# FLS_Hamamatsu_A.net
KiCad netlist of a schematic drawn in Altium Designer
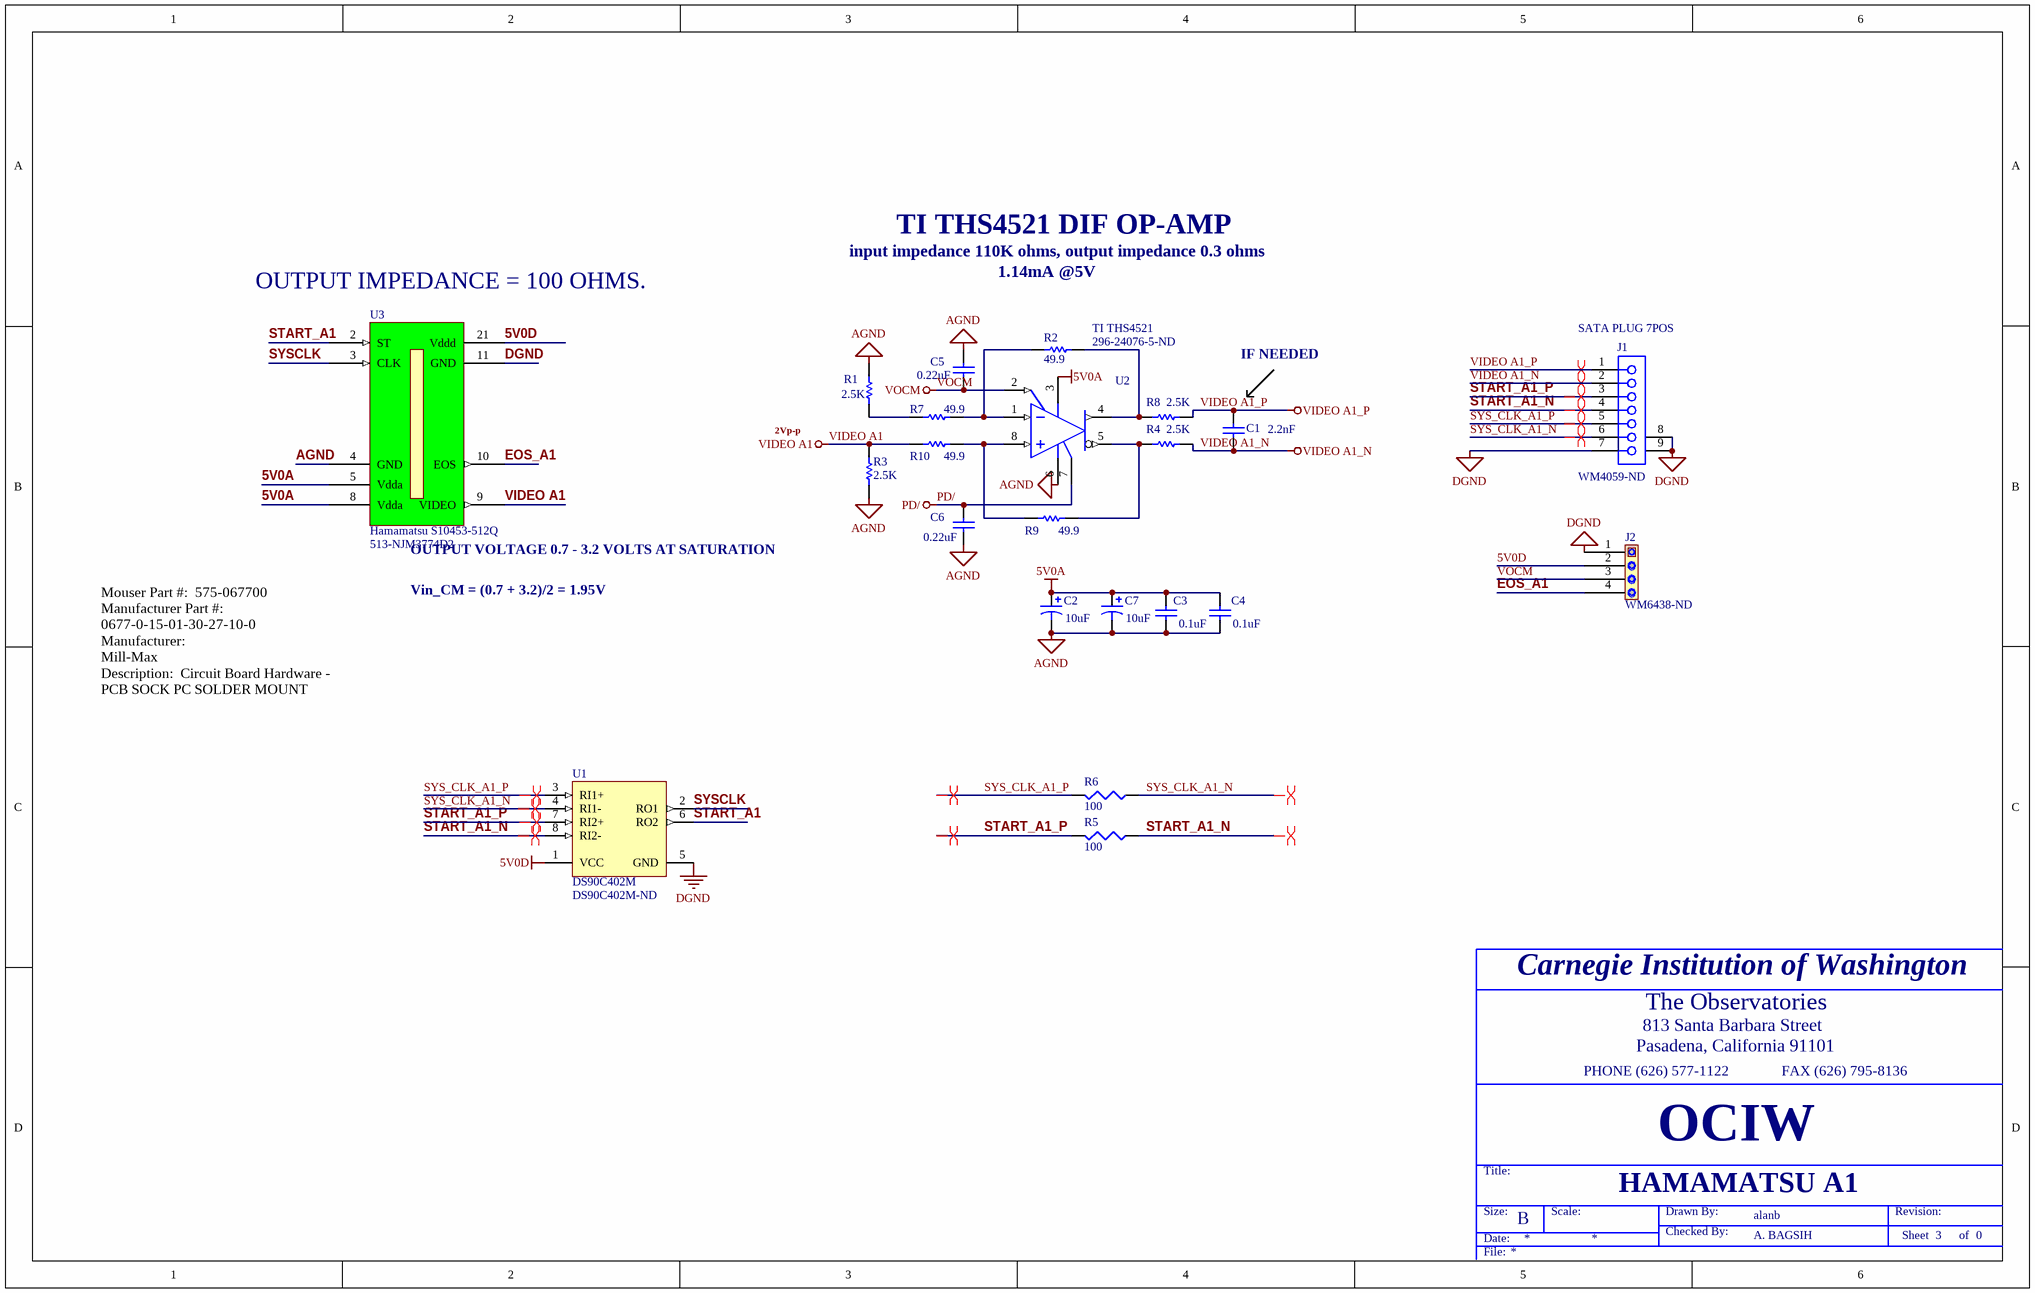
[diagram p0: FLS Hamamatsu_A.SchDoc]

(export (version "E")
  (design (tool "Eeschema 10.0.6"))
  (components
    (comp (ref "C1")
      (value "2.2nF")
      (footprint "0805 SLIM")
      (description "Capacitor")
      (fields (field (name "Comment") "Cap") (field (name "PUBLISHER") "Altium Limited"))
      (libsource (lib "Miscellaneous Devices") (part "Cap"))
    )
    (comp (ref "C2")
      (value "10uF")
      (footprint "1206")
      (description "CAP TANT 10UF 16V 20% 1206")
      (fields (field (name "Comment") "Cap Pol3") (field (name "PUBLISHER") "Altium Limited"))
      (libsource (lib "Miscellaneous Devices") (part "Cap Pol3"))
    )
    (comp (ref "C3")
      (value "0.1uF")
      (footprint "0805 SLIM")
      (description "Capacitor")
      (fields (field (name "Comment") "Cap") (field (name "PUBLISHER") "Altium Limited"))
      (libsource (lib "Miscellaneous Devices") (part "Cap"))
    )
    (comp (ref "C4")
      (value "0.1uF")
      (footprint "0805 SLIM")
      (description "Capacitor")
      (fields (field (name "Comment") "Cap") (field (name "PUBLISHER") "Altium Limited"))
      (libsource (lib "Miscellaneous Devices") (part "Cap"))
    )
    (comp (ref "C5")
      (value "0.22uF")
      (footprint "0805 SLIM")
      (description "CAP CER 0.22UF 50V 10% X7R 0805")
      (fields
        (field (name "DIGI-KEY PART NUMBER") "587-1287-6-ND")
        (field (name "PUBLISHER") "Altium Limited")
      )
      (libsource (lib "Miscellaneous Devices") (part "Cap"))
    )
    (comp (ref "C6")
      (value "0.22uF")
      (footprint "0805 SLIM")
      (description "CAP CER 0.22UF 50V 10% X7R 0805")
      (fields
        (field (name "DIGI-KEY PART NUMBER") "587-1287-6-ND")
        (field (name "PUBLISHER") "Altium Limited")
      )
      (libsource (lib "Miscellaneous Devices") (part "Cap"))
    )
    (comp (ref "C7")
      (value "10uF")
      (footprint "1206")
      (description "CAP TANT 10UF 16V 20% 1206")
      (fields (field (name "Comment") "Cap Pol3") (field (name "PUBLISHER") "Altium Limited"))
      (libsource (lib "Miscellaneous Devices") (part "Cap Pol3"))
    )
    (comp (ref "J1")
      (value "SATA PLUG 7POS")
      (footprint "Molex 471554001")
      (description "FH12 Series, \"Flip-Lock\" SMT/ZIF FFC/FPC Connector - 1.0mm Spaced Bottom Standard Contact")
      (fields
        (field (name "MANUFACTURER") "Molex Inc")
        (field (name "SUPPLIER PART NUMBER 1") "WM4059-ND")
        (field (name "PUBLISHER") "Altium Limited")
      )
      (libsource (lib "FLS HAMAMATSU_A PCB Aug_1_2012") (part "CL586-0535-5"))
    )
    (comp (ref "J2")
      (value "CON4")
      (footprint "SIP4")
      (fields (field (name "SUPPLIER PART NUMBER 1") "WM6438-ND"))
      (libsource (lib "FLS HAMAMATSU_A PCB 28 April 2012") (part "CON3"))
    )
    (comp (ref "R1")
      (value "2.5K")
      (footprint "0805 SLIM")
      (description "Thin Film Resistors - SMD 1/10W 2.5Kohm 0.1% 25ppm")
      (fields (field (name "TOLERANCE") "0.1 %") (field (name "PUBLISHER") "Altium Limited"))
      (libsource (lib "Miscellaneous Devices") (part "Res1"))
    )
    (comp (ref "R2")
      (value "49.9")
      (footprint "0805 SLIM")
      (description "RES 49.9 OHM 1/10W 0.1% 0805")
      (fields (field (name "TOLERANCE") "±0.1%") (field (name "PUBLISHER") "Altium Limited"))
      (libsource (lib "Miscellaneous Devices") (part "Res1"))
    )
    (comp (ref "R3")
      (value "2.5K")
      (footprint "0805 SLIM")
      (description "Thin Film Resistors - SMD 1/10W 2.5Kohm 0.1% 25ppm")
      (fields (field (name "TOLERANCE") "0.1 %") (field (name "PUBLISHER") "Altium Limited"))
      (libsource (lib "Miscellaneous Devices") (part "Res1"))
    )
    (comp (ref "R4")
      (value "2.5K")
      (footprint "0805 SLIM")
      (description "Thin Film Resistors - SMD 1/10W 2.5Kohm 0.1% 25ppm")
      (fields (field (name "TOLERANCE") "0.1 %") (field (name "PUBLISHER") "Altium Limited"))
      (libsource (lib "Miscellaneous Devices") (part "Res1"))
    )
    (comp (ref "R5") (value "100") (footprint "0402 slim") (libsource (lib "*") (part "RES1")))
    (comp (ref "R6") (value "100") (footprint "0402 SLIM") (libsource (lib "*") (part "RES1")))
    (comp (ref "R7")
      (value "49.9")
      (footprint "0805 SLIM")
      (description "RES 49.9 OHM 1/10W 0.1% 0805")
      (fields (field (name "TOLERANCE") "±0.1%") (field (name "PUBLISHER") "Altium Limited"))
      (libsource (lib "Miscellaneous Devices") (part "Res1"))
    )
    (comp (ref "R8")
      (value "2.5K")
      (footprint "0805 SLIM")
      (description "Thin Film Resistors - SMD 1/10W 2.5Kohm 0.1% 25ppm")
      (fields (field (name "TOLERANCE") "0.1 %") (field (name "PUBLISHER") "Altium Limited"))
      (libsource (lib "Miscellaneous Devices") (part "Res1"))
    )
    (comp (ref "R9")
      (value "49.9")
      (footprint "0805 SLIM")
      (description "RES 49.9 OHM 1/10W 0.1% 0805")
      (fields (field (name "TOLERANCE") "±0.1%") (field (name "PUBLISHER") "Altium Limited"))
      (libsource (lib "Miscellaneous Devices") (part "Res1"))
    )
    (comp (ref "R10")
      (value "49.9")
      (footprint "0805 SLIM")
      (description "RES 49.9 OHM 1/10W 0.1% 0805")
      (fields (field (name "TOLERANCE") "±0.1%") (field (name "PUBLISHER") "Altium Limited"))
      (libsource (lib "Miscellaneous Devices") (part "Res1"))
    )
    (comp (ref "U1")
      (value "DS90C402M")
      (footprint "M08A_N")
      (description "Dual Low Voltage Differential Signaling (LVDS) Receiver, 8-pin Narrow SOIC")
      (fields
        (field (name "SUPPLIER PART NUMBER 1") "DS90C402M-ND")
        (field (name "MANUFACTURER") "National Semiconductor")
        (field (name "PUBLISHER") "Altium Limited")
      )
      (libsource (lib "FLS HAMAMATSU_A PCB 28 April 2012") (part "DS90C402M"))
    )
    (comp (ref "U2")
      (value "TI THS4521")
      (footprint "Zetex Discrete MOSFET:MSOP8")
      (description "IC OPAMP DIFF R-R 145MHZ 8MSOP")
      (fields
        (field (name "DIGI-KEY PART NUMBER") "296-24077-6-ND")
        (field (name "MANUFACTURER") "TEXAS INSTRUMENTS")
        (field (name "SUPPLIER PART NUMBER 1") "296-24076-5-ND")
      )
      (libsource (lib "FLS HAMAMATSU_A PCB Aug_1_2012") (part "TI THS4521"))
    )
    (comp (ref "U3")
      (value "Hamamatsu S10453-512Q")
      (footprint "Hamamatsu 22")
      (description "Linear Image Sensor")
      (fields (field (name "SUPPLIER PART NUMBER 1") "513-NJM3774D2"))
      (libsource (lib "FLS HAMAMATSU_A PCB Aug_1_2012") (part "Hamamatsu"))
    )
  )
  (nets
    (net (code "1") (name "/EOS_A1") (class "Default")
      (node (ref "J2") (pin "4") (pinfunction "4_4") (pintype "power_in"))
      (node (ref "U3") (pin "10") (pinfunction "EOS_10") (pintype "output"))
    )
    (net (code "2") (name "/START_A1") (class "Default")
      (node (ref "U1") (pin "6") (pinfunction "RO2_6") (pintype "output"))
      (node (ref "U3") (pin "2") (pinfunction "ST_2") (pintype "input"))
    )
    (net (code "3") (name "/START_A1_N") (class "Default")
      (node (ref "J1") (pin "4") (pinfunction "4_4") (pintype "passive"))
      (node (ref "R5") (pin "1") (pintype "passive"))
      (node (ref "U1") (pin "8") (pinfunction "RI2-_8") (pintype "input"))
    )
    (net (code "4") (name "/START_A1_P") (class "Default")
      (node (ref "J1") (pin "3") (pinfunction "3_3") (pintype "passive"))
      (node (ref "R5") (pin "2") (pintype "passive"))
      (node (ref "U1") (pin "7") (pinfunction "RI2+_7") (pintype "input"))
    )
    (net (code "5") (name "/SYSCLK") (class "Default")
      (node (ref "U1") (pin "2") (pinfunction "RO1_2") (pintype "output"))
      (node (ref "U3") (pin "3") (pinfunction "CLK_3") (pintype "input"))
    )
    (net (code "6") (name "/SYS_CLK_A1_N") (class "Default")
      (node (ref "J1") (pin "6") (pinfunction "6_6") (pintype "passive"))
      (node (ref "R6") (pin "1") (pintype "passive"))
      (node (ref "U1") (pin "4") (pinfunction "RI1-_4") (pintype "input"))
    )
    (net (code "7") (name "/SYS_CLK_A1_P") (class "Default")
      (node (ref "J1") (pin "5") (pinfunction "5_5") (pintype "passive"))
      (node (ref "R6") (pin "2") (pintype "passive"))
      (node (ref "U1") (pin "3") (pinfunction "RI1+_3") (pintype "input"))
    )
    (net (code "8") (name "5V0A") (class "Default")
      (node (ref "C2") (pin "1") (pinfunction "1_1") (pintype "passive"))
      (node (ref "C3") (pin "2") (pinfunction "2_2") (pintype "passive"))
      (node (ref "C4") (pin "2") (pinfunction "2_2") (pintype "passive"))
      (node (ref "C7") (pin "1") (pinfunction "1_1") (pintype "passive"))
      (node (ref "U2") (pin "3") (pinfunction "V+_3") (pintype "power_in"))
      (node (ref "U3") (pin "5") (pinfunction "Vdda_5") (pintype "power_in"))
      (node (ref "U3") (pin "8") (pinfunction "Vdda_8") (pintype "power_in"))
    )
    (net (code "9") (name "5V0D") (class "Default")
      (node (ref "J2") (pin "2") (pinfunction "2_2") (pintype "power_in"))
      (node (ref "U1") (pin "1") (pinfunction "VCC_1") (pintype "power_in"))
      (node (ref "U3") (pin "21") (pinfunction "Vddd_21") (pintype "power_in"))
    )
    (net (code "10") (name "AGND") (class "Default")
      (node (ref "C2") (pin "2") (pinfunction "2_2") (pintype "passive"))
      (node (ref "C3") (pin "1") (pinfunction "1_1") (pintype "passive"))
      (node (ref "C4") (pin "1") (pinfunction "1_1") (pintype "passive"))
      (node (ref "C5") (pin "2") (pinfunction "2_2") (pintype "passive"))
      (node (ref "C6") (pin "1") (pinfunction "1_1") (pintype "passive"))
      (node (ref "C7") (pin "2") (pinfunction "2_2") (pintype "passive"))
      (node (ref "R1") (pin "1") (pinfunction "1_1") (pintype "passive"))
      (node (ref "R3") (pin "2") (pinfunction "2_2") (pintype "passive"))
      (node (ref "U2") (pin "6") (pinfunction "V-_6") (pintype "power_in"))
      (node (ref "U3") (pin "4") (pinfunction "GND_4") (pintype "power_in"))
    )
    (net (code "11") (name "DGND") (class "Default")
      (node (ref "J1") (pin "7") (pinfunction "7_7") (pintype "passive"))
      (node (ref "J1") (pin "8") (pinfunction "MH1_8") (pintype "passive"))
      (node (ref "J1") (pin "9") (pinfunction "MH2_9") (pintype "passive"))
      (node (ref "J2") (pin "1") (pinfunction "1_1") (pintype "power_in"))
      (node (ref "U1") (pin "5") (pinfunction "GND_5") (pintype "power_in"))
      (node (ref "U3") (pin "11") (pinfunction "GND_11") (pintype "power_in"))
    )
    (net (code "12") (name "Net-(R1-Pad2)") (class "Default")
      (node (ref "R1") (pin "2") (pinfunction "2_2") (pintype "passive"))
      (node (ref "R7") (pin "1") (pinfunction "1_1") (pintype "passive"))
    )
    (net (code "13") (name "Net-(U2-IN+)") (class "Default")
      (node (ref "R10") (pin "2") (pinfunction "2_2") (pintype "passive"))
      (node (ref "R9") (pin "1") (pinfunction "1_1") (pintype "passive"))
      (node (ref "U2") (pin "8") (pinfunction "IN+_8") (pintype "input"))
    )
    (net (code "14") (name "Net-(U2-IN-)") (class "Default")
      (node (ref "R2") (pin "1") (pinfunction "1_1") (pintype "passive"))
      (node (ref "R7") (pin "2") (pinfunction "2_2") (pintype "passive"))
      (node (ref "U2") (pin "1") (pinfunction "IN-_1") (pintype "input"))
    )
    (net (code "15") (name "Net-(U2-Q)") (class "Default")
      (node (ref "R2") (pin "2") (pinfunction "2_2") (pintype "passive"))
      (node (ref "R8") (pin "2") (pinfunction "2_2") (pintype "passive"))
      (node (ref "U2") (pin "4") (pinfunction "Q_4") (pintype "output"))
    )
    (net (code "16") (name "Net-(U2-~{Q})") (class "Default")
      (node (ref "R4") (pin "2") (pinfunction "2_2") (pintype "passive"))
      (node (ref "R9") (pin "2") (pinfunction "2_2") (pintype "passive"))
      (node (ref "U2") (pin "5") (pinfunction "~{Q}_5") (pintype "output"))
    )
    (net (code "17") (name "PD{slash}") (class "Default")
      (node (ref "C6") (pin "2") (pinfunction "2_2") (pintype "passive"))
      (node (ref "U2") (pin "7") (pinfunction "PD/_7") (pintype "power_in"))
    )
    (net (code "18") (name "VIDEO A1") (class "Default")
      (node (ref "R10") (pin "1") (pinfunction "1_1") (pintype "passive"))
      (node (ref "R3") (pin "1") (pinfunction "1_1") (pintype "passive"))
      (node (ref "U3") (pin "9") (pinfunction "VIDEO_9") (pintype "output"))
    )
    (net (code "19") (name "VIDEO A1_N") (class "Default")
      (node (ref "C1") (pin "1") (pinfunction "1_1") (pintype "passive"))
      (node (ref "J1") (pin "2") (pinfunction "2_2") (pintype "passive"))
      (node (ref "R4") (pin "1") (pinfunction "1_1") (pintype "passive"))
    )
    (net (code "20") (name "VIDEO A1_P") (class "Default")
      (node (ref "C1") (pin "2") (pinfunction "2_2") (pintype "passive"))
      (node (ref "J1") (pin "1") (pinfunction "1_1") (pintype "passive"))
      (node (ref "R8") (pin "1") (pinfunction "1_1") (pintype "passive"))
    )
    (net (code "21") (name "VOCM") (class "Default")
      (node (ref "C5") (pin "1") (pinfunction "1_1") (pintype "passive"))
      (node (ref "J2") (pin "3") (pinfunction "3_3") (pintype "power_in"))
      (node (ref "U2") (pin "2") (pinfunction "Vocm_2") (pintype "input"))
    )
  )
)
